# NCS_Wireless_Indicator_DIP_HC12_Prog.net
KiCad netlist of a schematic drawn in Altium Designer
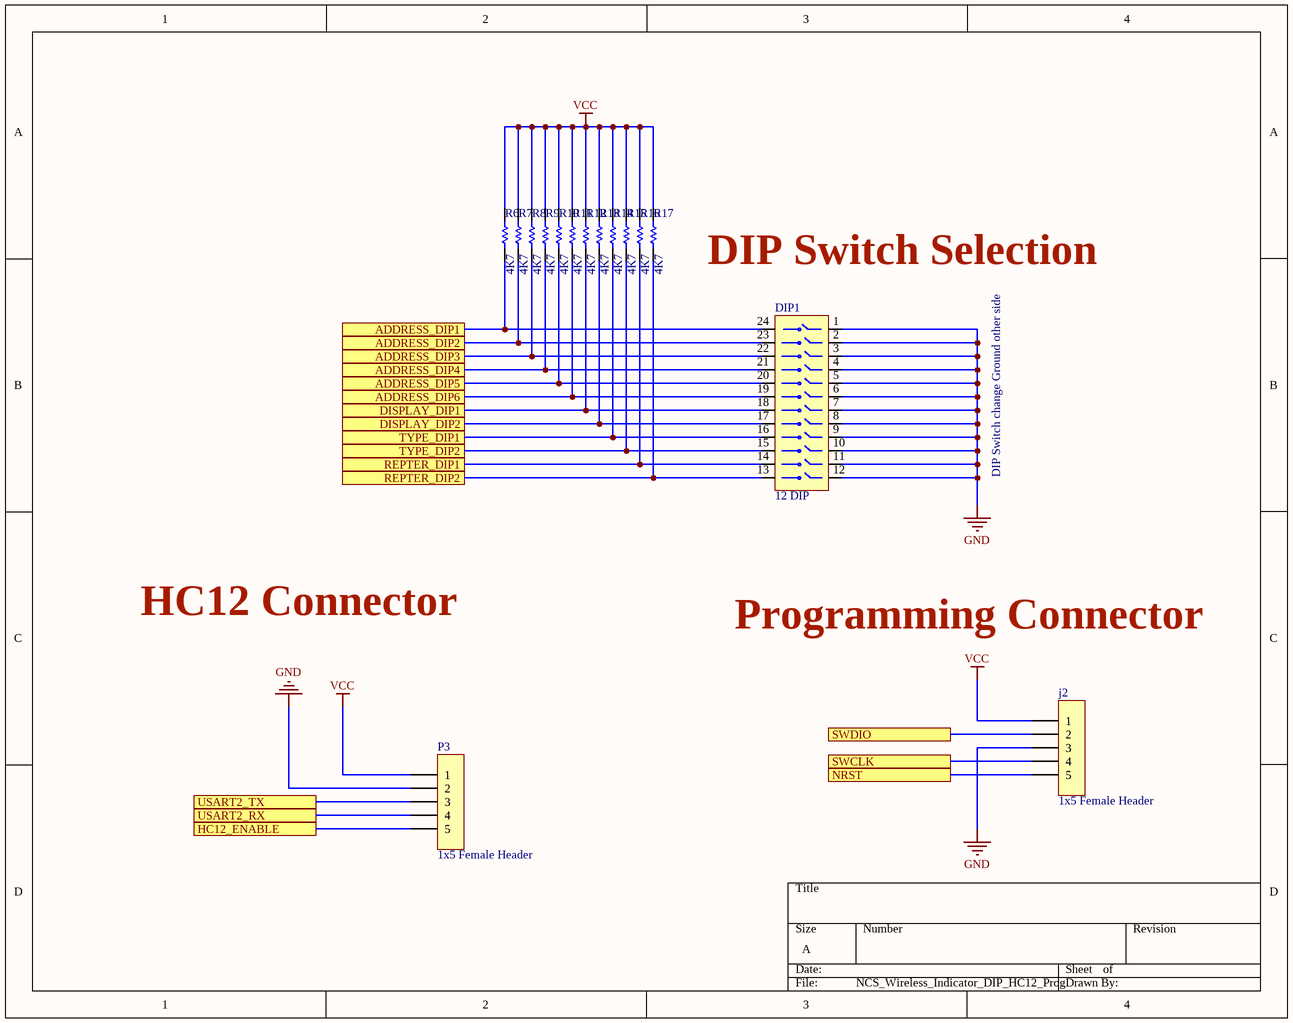
[diagram p0: NCS_Wireless_Indicator_DIP_HC12_Prog.SchDoc]

(export (version "E")
  (design (tool "Eeschema 10.0.6"))
  (components
    (comp (ref "DIP1")
      (value "12 DIP")
      (footprint "DIP24")
      (libsource (lib "NCS_Wireless_Bed_Unit") (part "12 Way 2.54MM DIP switch - SUNROM"))
    )
    (comp (ref "j2")
      (value "1x5 Female Header")
      (footprint "1x5 Female Header")
      (description "2.54mm (0.1) Pitch SIL Vertical PC Tail Pin Header, 6.1mm mating pin height, tin, 5 contacts\"")
      (fields (field (name "MANUFACTURER") "Harwin") (field (name "MANUFACTURER PART NUMBER") "M20-9990546"))
      (libsource (lib "schlib") (part "M20-9990546"))
    )
    (comp (ref "P3")
      (value "1x5 Female Header")
      (footprint "1x5 Female Header")
      (description "2.54mm (0.1) Pitch SIL Vertical PC Tail Pin Header, 6.1mm mating pin height, tin, 5 contacts\"")
      (fields (field (name "MANUFACTURER") "Harwin") (field (name "MANUFACTURER PART NUMBER") "M20-9990546"))
      (libsource (lib "schlib") (part "M20-9990546"))
    )
    (comp (ref "R6")
      (value "4K7")
      (footprint "RC0805FR-7W4K7L")
      (description "SMD Chip Resistor, 4.7 kOhm, ± 1%, 250 mW, 0805 [2012 Metric], Thick Film, General Purpose")
      (fields
        (field (name "MANUFACTURER") "Yageo")
        (field (name "MANUFACTURER PART NUMBER") "RC0805FR-7W4K7L")
      )
      (libsource (lib "schlib") (part "RC0805FR-7W4K7L"))
    )
    (comp (ref "R7")
      (value "4K7")
      (footprint "RC0805FR-7W4K7L")
      (description "SMD Chip Resistor, 4.7 kOhm, ± 1%, 250 mW, 0805 [2012 Metric], Thick Film, General Purpose")
      (fields
        (field (name "MANUFACTURER") "Yageo")
        (field (name "MANUFACTURER PART NUMBER") "RC0805FR-7W4K7L")
      )
      (libsource (lib "schlib") (part "RC0805FR-7W4K7L"))
    )
    (comp (ref "R8")
      (value "4K7")
      (footprint "RC0805FR-7W4K7L")
      (description "SMD Chip Resistor, 4.7 kOhm, ± 1%, 250 mW, 0805 [2012 Metric], Thick Film, General Purpose")
      (fields
        (field (name "MANUFACTURER") "Yageo")
        (field (name "MANUFACTURER PART NUMBER") "RC0805FR-7W4K7L")
      )
      (libsource (lib "schlib") (part "RC0805FR-7W4K7L"))
    )
    (comp (ref "R9")
      (value "4K7")
      (footprint "RC0805FR-7W4K7L")
      (description "SMD Chip Resistor, 4.7 kOhm, ± 1%, 250 mW, 0805 [2012 Metric], Thick Film, General Purpose")
      (fields
        (field (name "MANUFACTURER") "Yageo")
        (field (name "MANUFACTURER PART NUMBER") "RC0805FR-7W4K7L")
      )
      (libsource (lib "schlib") (part "RC0805FR-7W4K7L"))
    )
    (comp (ref "R10")
      (value "4K7")
      (footprint "RC0805FR-7W4K7L")
      (description "SMD Chip Resistor, 4.7 kOhm, ± 1%, 250 mW, 0805 [2012 Metric], Thick Film, General Purpose")
      (fields
        (field (name "MANUFACTURER") "Yageo")
        (field (name "MANUFACTURER PART NUMBER") "RC0805FR-7W4K7L")
      )
      (libsource (lib "schlib") (part "RC0805FR-7W4K7L"))
    )
    (comp (ref "R11")
      (value "4K7")
      (footprint "RC0805FR-7W4K7L")
      (description "SMD Chip Resistor, 4.7 kOhm, ± 1%, 250 mW, 0805 [2012 Metric], Thick Film, General Purpose")
      (fields
        (field (name "MANUFACTURER") "Yageo")
        (field (name "MANUFACTURER PART NUMBER") "RC0805FR-7W4K7L")
      )
      (libsource (lib "schlib") (part "RC0805FR-7W4K7L"))
    )
    (comp (ref "R12")
      (value "4K7")
      (footprint "RC0805FR-7W4K7L")
      (description "SMD Chip Resistor, 4.7 kOhm, ± 1%, 250 mW, 0805 [2012 Metric], Thick Film, General Purpose")
      (fields
        (field (name "MANUFACTURER") "Yageo")
        (field (name "MANUFACTURER PART NUMBER") "RC0805FR-7W4K7L")
      )
      (libsource (lib "schlib") (part "RC0805FR-7W4K7L"))
    )
    (comp (ref "R13")
      (value "4K7")
      (footprint "RC0805FR-7W4K7L")
      (description "SMD Chip Resistor, 4.7 kOhm, ± 1%, 250 mW, 0805 [2012 Metric], Thick Film, General Purpose")
      (fields
        (field (name "MANUFACTURER") "Yageo")
        (field (name "MANUFACTURER PART NUMBER") "RC0805FR-7W4K7L")
      )
      (libsource (lib "schlib") (part "RC0805FR-7W4K7L"))
    )
    (comp (ref "R14")
      (value "4K7")
      (footprint "RC0805FR-7W4K7L")
      (description "SMD Chip Resistor, 4.7 kOhm, ± 1%, 250 mW, 0805 [2012 Metric], Thick Film, General Purpose")
      (fields
        (field (name "MANUFACTURER") "Yageo")
        (field (name "MANUFACTURER PART NUMBER") "RC0805FR-7W4K7L")
      )
      (libsource (lib "schlib") (part "RC0805FR-7W4K7L"))
    )
    (comp (ref "R15")
      (value "4K7")
      (footprint "RC0805FR-7W4K7L")
      (description "SMD Chip Resistor, 4.7 kOhm, ± 1%, 250 mW, 0805 [2012 Metric], Thick Film, General Purpose")
      (fields
        (field (name "MANUFACTURER") "Yageo")
        (field (name "MANUFACTURER PART NUMBER") "RC0805FR-7W4K7L")
      )
      (libsource (lib "schlib") (part "RC0805FR-7W4K7L"))
    )
    (comp (ref "R16")
      (value "4K7")
      (footprint "RC0805FR-7W4K7L")
      (description "SMD Chip Resistor, 4.7 kOhm, ± 1%, 250 mW, 0805 [2012 Metric], Thick Film, General Purpose")
      (fields
        (field (name "MANUFACTURER") "Yageo")
        (field (name "MANUFACTURER PART NUMBER") "RC0805FR-7W4K7L")
      )
      (libsource (lib "schlib") (part "RC0805FR-7W4K7L"))
    )
    (comp (ref "R17")
      (value "4K7")
      (footprint "RC0805FR-7W4K7L")
      (description "SMD Chip Resistor, 4.7 kOhm, ± 1%, 250 mW, 0805 [2012 Metric], Thick Film, General Purpose")
      (fields
        (field (name "MANUFACTURER") "Yageo")
        (field (name "MANUFACTURER PART NUMBER") "RC0805FR-7W4K7L")
      )
      (libsource (lib "schlib") (part "RC0805FR-7W4K7L"))
    )
  )
  (nets
    (net (code "1") (name "/ADDRESS_DIP1") (class "Default")
      (node (ref "DIP1") (pin "24") (pinfunction "24_24") (pintype "passive"))
      (node (ref "R6") (pin "2") (pinfunction "2_2") (pintype "passive"))
    )
    (net (code "2") (name "/ADDRESS_DIP2") (class "Default")
      (node (ref "DIP1") (pin "23") (pinfunction "23_23") (pintype "passive"))
      (node (ref "R7") (pin "2") (pinfunction "2_2") (pintype "passive"))
    )
    (net (code "3") (name "/ADDRESS_DIP3") (class "Default")
      (node (ref "DIP1") (pin "22") (pinfunction "22_22") (pintype "passive"))
      (node (ref "R8") (pin "2") (pinfunction "2_2") (pintype "passive"))
    )
    (net (code "4") (name "/ADDRESS_DIP4") (class "Default")
      (node (ref "DIP1") (pin "21") (pinfunction "21_21") (pintype "passive"))
      (node (ref "R9") (pin "2") (pinfunction "2_2") (pintype "passive"))
    )
    (net (code "5") (name "/ADDRESS_DIP5") (class "Default")
      (node (ref "DIP1") (pin "20") (pinfunction "20_20") (pintype "passive"))
      (node (ref "R10") (pin "2") (pinfunction "2_2") (pintype "passive"))
    )
    (net (code "6") (name "/ADDRESS_DIP6") (class "Default")
      (node (ref "DIP1") (pin "19") (pinfunction "19_19") (pintype "passive"))
      (node (ref "R11") (pin "2") (pinfunction "2_2") (pintype "passive"))
    )
    (net (code "7") (name "/DISPLAY_DIP1") (class "Default")
      (node (ref "DIP1") (pin "18") (pinfunction "18_18") (pintype "passive"))
      (node (ref "R12") (pin "2") (pinfunction "2_2") (pintype "passive"))
    )
    (net (code "8") (name "/DISPLAY_DIP2") (class "Default")
      (node (ref "DIP1") (pin "17") (pinfunction "17_17") (pintype "passive"))
      (node (ref "R13") (pin "2") (pinfunction "2_2") (pintype "passive"))
    )
    (net (code "9") (name "/HC12_ENABLE") (class "Default")
      (node (ref "P3") (pin "5") (pinfunction "5_5") (pintype "passive"))
    )
    (net (code "10") (name "/NRST") (class "Default")
      (node (ref "j2") (pin "5") (pinfunction "5_5") (pintype "passive"))
    )
    (net (code "11") (name "/REPTER_DIP1") (class "Default")
      (node (ref "DIP1") (pin "14") (pinfunction "14_14") (pintype "passive"))
      (node (ref "R16") (pin "2") (pinfunction "2_2") (pintype "passive"))
    )
    (net (code "12") (name "/REPTER_DIP2") (class "Default")
      (node (ref "DIP1") (pin "13") (pinfunction "13_13") (pintype "passive"))
      (node (ref "R17") (pin "2") (pinfunction "2_2") (pintype "passive"))
    )
    (net (code "13") (name "/SWCLK") (class "Default")
      (node (ref "j2") (pin "4") (pinfunction "4_4") (pintype "passive"))
    )
    (net (code "14") (name "/SWDIO") (class "Default")
      (node (ref "j2") (pin "2") (pinfunction "2_2") (pintype "passive"))
    )
    (net (code "15") (name "/TYPE_DIP1") (class "Default")
      (node (ref "DIP1") (pin "16") (pinfunction "16_16") (pintype "passive"))
      (node (ref "R14") (pin "2") (pinfunction "2_2") (pintype "passive"))
    )
    (net (code "16") (name "/TYPE_DIP2") (class "Default")
      (node (ref "DIP1") (pin "15") (pinfunction "15_15") (pintype "passive"))
      (node (ref "R15") (pin "2") (pinfunction "2_2") (pintype "passive"))
    )
    (net (code "17") (name "/USART2_RX") (class "Default")
      (node (ref "P3") (pin "4") (pinfunction "4_4") (pintype "passive"))
    )
    (net (code "18") (name "/USART2_TX") (class "Default")
      (node (ref "P3") (pin "3") (pinfunction "3_3") (pintype "passive"))
    )
    (net (code "19") (name "GND") (class "Default")
      (node (ref "DIP1") (pin "1") (pinfunction "1_1") (pintype "passive"))
      (node (ref "DIP1") (pin "10") (pinfunction "10_10") (pintype "passive"))
      (node (ref "DIP1") (pin "11") (pinfunction "11_11") (pintype "passive"))
      (node (ref "DIP1") (pin "12") (pinfunction "12_12") (pintype "passive"))
      (node (ref "DIP1") (pin "2") (pinfunction "2_2") (pintype "passive"))
      (node (ref "DIP1") (pin "3") (pinfunction "3_3") (pintype "passive"))
      (node (ref "DIP1") (pin "4") (pinfunction "4_4") (pintype "passive"))
      (node (ref "DIP1") (pin "5") (pinfunction "5_5") (pintype "passive"))
      (node (ref "DIP1") (pin "6") (pinfunction "6_6") (pintype "passive"))
      (node (ref "DIP1") (pin "7") (pinfunction "7_7") (pintype "passive"))
      (node (ref "DIP1") (pin "8") (pinfunction "8_8") (pintype "passive"))
      (node (ref "DIP1") (pin "9") (pinfunction "9_9") (pintype "passive"))
      (node (ref "P3") (pin "2") (pinfunction "2_2") (pintype "passive"))
      (node (ref "j2") (pin "3") (pinfunction "3_3") (pintype "passive"))
    )
    (net (code "20") (name "VCC") (class "Default")
      (node (ref "P3") (pin "1") (pinfunction "1_1") (pintype "passive"))
      (node (ref "R10") (pin "1") (pinfunction "1_1") (pintype "passive"))
      (node (ref "R11") (pin "1") (pinfunction "1_1") (pintype "passive"))
      (node (ref "R12") (pin "1") (pinfunction "1_1") (pintype "passive"))
      (node (ref "R13") (pin "1") (pinfunction "1_1") (pintype "passive"))
      (node (ref "R14") (pin "1") (pinfunction "1_1") (pintype "passive"))
      (node (ref "R15") (pin "1") (pinfunction "1_1") (pintype "passive"))
      (node (ref "R16") (pin "1") (pinfunction "1_1") (pintype "passive"))
      (node (ref "R17") (pin "1") (pinfunction "1_1") (pintype "passive"))
      (node (ref "R6") (pin "1") (pinfunction "1_1") (pintype "passive"))
      (node (ref "R7") (pin "1") (pinfunction "1_1") (pintype "passive"))
      (node (ref "R8") (pin "1") (pinfunction "1_1") (pintype "passive"))
      (node (ref "R9") (pin "1") (pinfunction "1_1") (pintype "passive"))
      (node (ref "j2") (pin "1") (pinfunction "1_1") (pintype "passive"))
    )
  )
)
